# EEPROM.net
KiCad netlist of a schematic drawn in Altium Designer
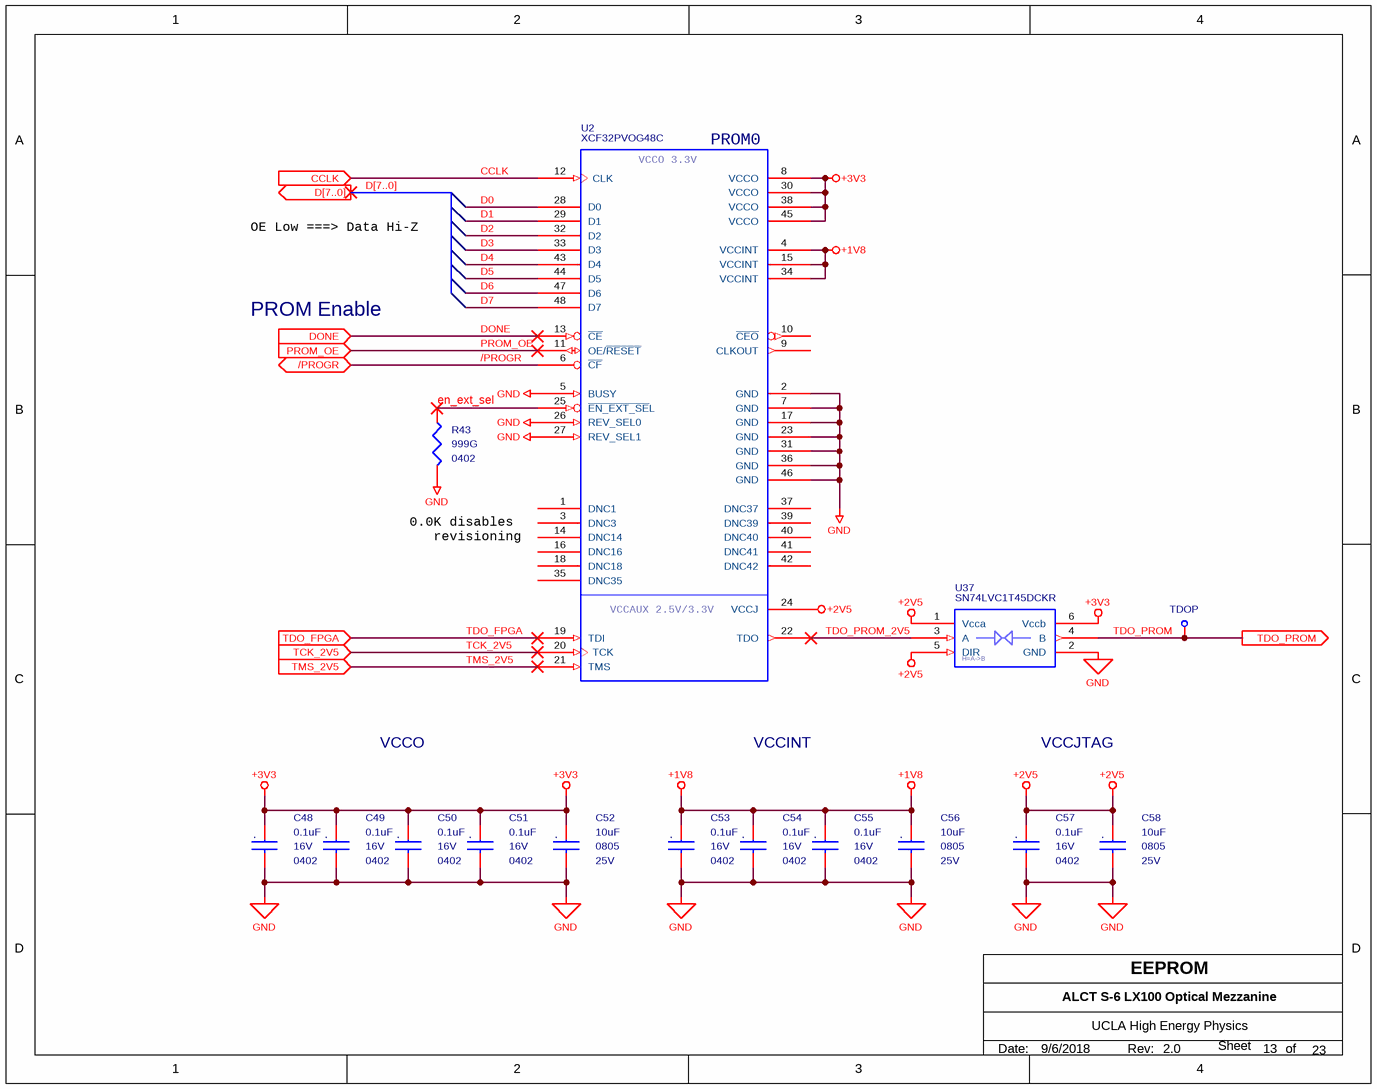
[diagram p0: EEPROM.SchDoc]

(export (version "E")
  (design (tool "Eeschema 10.0.6"))
  (components
    (comp (ref "C48")
      (value "0.1uF")
      (footprint "MC_S6/SM/C_0402_IPC")
      (description "CAP CER 0.1UF 16V X7R 0402")
      (fields
        (field (name "MANUFACTURER") "KEMET")
        (field (name "MANUFACTURER PART NUMBER") "C0402C104K4RACTU")
        (field (name "PACKAGE") "0402")
        (field (name "VOLTAGE - RATED") "16V")
      )
      (libsource (lib "ALCT_MEZ_SPARTAN6_Library") (part "C0402C104K4RACTU"))
    )
    (comp (ref "C49")
      (value "0.1uF")
      (footprint "MC_S6/SM/C_0402_IPC")
      (description "CAP CER 0.1UF 16V X7R 0402")
      (fields
        (field (name "MANUFACTURER") "KEMET")
        (field (name "MANUFACTURER PART NUMBER") "C0402C104K4RACTU")
        (field (name "PACKAGE") "0402")
        (field (name "VOLTAGE - RATED") "16V")
      )
      (libsource (lib "ALCT_MEZ_SPARTAN6_Library") (part "C0402C104K4RACTU"))
    )
    (comp (ref "C50")
      (value "0.1uF")
      (footprint "MC_S6/SM/C_0402_IPC")
      (description "CAP CER 0.1UF 16V X7R 0402")
      (fields
        (field (name "MANUFACTURER") "KEMET")
        (field (name "MANUFACTURER PART NUMBER") "C0402C104K4RACTU")
        (field (name "PACKAGE") "0402")
        (field (name "VOLTAGE - RATED") "16V")
      )
      (libsource (lib "ALCT_MEZ_SPARTAN6_Library") (part "C0402C104K4RACTU"))
    )
    (comp (ref "C51")
      (value "0.1uF")
      (footprint "MC_S6/SM/C_0402_IPC")
      (description "CAP CER 0.1UF 16V X7R 0402")
      (fields
        (field (name "MANUFACTURER") "KEMET")
        (field (name "MANUFACTURER PART NUMBER") "C0402C104K4RACTU")
        (field (name "PACKAGE") "0402")
        (field (name "VOLTAGE - RATED") "16V")
      )
      (libsource (lib "ALCT_MEZ_SPARTAN6_Library") (part "C0402C104K4RACTU"))
    )
    (comp (ref "C52")
      (value "10uF")
      (footprint "MC_S6/SM/C_0805_IPC")
      (description "CAP CER 10UF 25V X5R 0805")
      (fields
        (field (name "MANUFACTURER") "Murata Electronics North America")
        (field (name "MANUFACTURER PART NUMBER") "GRM21BR61E106KA73L")
        (field (name "VOLTAGE - RATED") "25V")
        (field (name "PACKAGE") "0805")
      )
      (libsource (lib "ALCT_MEZ_SPARTAN6_Library") (part "GRM21BR61E106KA73L"))
    )
    (comp (ref "C53")
      (value "0.1uF")
      (footprint "MC_S6/SM/C_0402_IPC")
      (description "CAP CER 0.1UF 16V X7R 0402")
      (fields
        (field (name "MANUFACTURER") "KEMET")
        (field (name "MANUFACTURER PART NUMBER") "C0402C104K4RACTU")
        (field (name "PACKAGE") "0402")
        (field (name "VOLTAGE - RATED") "16V")
      )
      (libsource (lib "ALCT_MEZ_SPARTAN6_Library") (part "C0402C104K4RACTU"))
    )
    (comp (ref "C54")
      (value "0.1uF")
      (footprint "MC_S6/SM/C_0402_IPC")
      (description "CAP CER 0.1UF 16V X7R 0402")
      (fields
        (field (name "MANUFACTURER") "KEMET")
        (field (name "MANUFACTURER PART NUMBER") "C0402C104K4RACTU")
        (field (name "PACKAGE") "0402")
        (field (name "VOLTAGE - RATED") "16V")
      )
      (libsource (lib "ALCT_MEZ_SPARTAN6_Library") (part "C0402C104K4RACTU"))
    )
    (comp (ref "C55")
      (value "0.1uF")
      (footprint "MC_S6/SM/C_0402_IPC")
      (description "CAP CER 0.1UF 16V X7R 0402")
      (fields
        (field (name "MANUFACTURER") "KEMET")
        (field (name "MANUFACTURER PART NUMBER") "C0402C104K4RACTU")
        (field (name "PACKAGE") "0402")
        (field (name "VOLTAGE - RATED") "16V")
      )
      (libsource (lib "ALCT_MEZ_SPARTAN6_Library") (part "C0402C104K4RACTU"))
    )
    (comp (ref "C56")
      (value "10uF")
      (footprint "MC_S6/SM/C_0805_IPC")
      (description "CAP CER 10UF 25V X5R 0805")
      (fields
        (field (name "MANUFACTURER") "Murata Electronics North America")
        (field (name "MANUFACTURER PART NUMBER") "GRM21BR61E106KA73L")
        (field (name "VOLTAGE - RATED") "25V")
        (field (name "PACKAGE") "0805")
      )
      (libsource (lib "ALCT_MEZ_SPARTAN6_Library") (part "GRM21BR61E106KA73L"))
    )
    (comp (ref "C57")
      (value "0.1uF")
      (footprint "MC_S6/SM/C_0402_IPC")
      (description "CAP CER 0.1UF 16V X7R 0402")
      (fields
        (field (name "MANUFACTURER") "KEMET")
        (field (name "MANUFACTURER PART NUMBER") "C0402C104K4RACTU")
        (field (name "PACKAGE") "0402")
        (field (name "VOLTAGE - RATED") "16V")
      )
      (libsource (lib "ALCT_MEZ_SPARTAN6_Library") (part "C0402C104K4RACTU"))
    )
    (comp (ref "C58")
      (value "10uF")
      (footprint "MC_S6/SM/C_0805_IPC")
      (description "CAP CER 10UF 25V X5R 0805")
      (fields
        (field (name "MANUFACTURER") "Murata Electronics North America")
        (field (name "MANUFACTURER PART NUMBER") "GRM21BR61E106KA73L")
        (field (name "VOLTAGE - RATED") "25V")
        (field (name "PACKAGE") "0805")
      )
      (libsource (lib "ALCT_MEZ_SPARTAN6_Library") (part "GRM21BR61E106KA73L"))
    )
    (comp (ref "R43")
      (value "999G")
      (footprint "MC_S6/SM/R_0402_IPC")
      (description "RES SMD 999G OHM 5% 1/16W 0402")
      (fields
        (field (name "MANUFACTURER PART NUMBER") "Do Not Place")
        (field (name "SUPPLIER DEVICE PACKAGE") "0402")
      )
      (libsource (lib "ALCT_MEZ_SPARTAN6_Library") (part "RES999G 0402"))
    )
    (comp (ref "TDOP")
      (value "Test Point Via")
      (footprint "MC_S6/TH/TPVIA")
      (libsource (lib "ALCT_MEZ_SPARTAN6_Library") (part "TPVIA"))
    )
    (comp (ref "U2")
      (value "XCF32PVOG48C")
      (footprint "MC_S6/SM/VOG48")
      (description "IC PROM SRL/PAR 1.8V 32M 48TSOP")
      (fields (field (name "MANUFACTURER") "Xilinx Inc."))
      (libsource (lib "ALCT_MEZ_SPARTAN6_Library") (part "XCF32PVOG48C"))
    )
    (comp (ref "U37")
      (value "SN74LVC1T45DCKR")
      (footprint "MC_S6/SM/SOT_SC70_DCK6")
      (description "IC BUS TRANSCVR TRI-ST SC70-6")
      (fields (field (name "MANUFACTURER") "Texas Instruments"))
      (libsource (lib "ALCT_MEZ_SPARTAN6_Library") (part "SN74LVC1T45-EP-ALCT_1"))
    )
  )
  (nets
    (net (code "1") (name "+1V8") (class "Default")
      (node (ref "C53") (pin "1") (pinfunction "1_1") (pintype "passive"))
      (node (ref "C54") (pin "1") (pinfunction "1_1") (pintype "passive"))
      (node (ref "C55") (pin "1") (pinfunction "1_1") (pintype "passive"))
      (node (ref "C56") (pin "1") (pinfunction "1_1") (pintype "passive"))
      (node (ref "U2") (pin "15") (pinfunction "VCCINT_15") (pintype "power_in"))
      (node (ref "U2") (pin "34") (pinfunction "VCCINT_34") (pintype "power_in"))
      (node (ref "U2") (pin "4") (pinfunction "VCCINT_4") (pintype "power_in"))
    )
    (net (code "2") (name "+2V5") (class "Default")
      (node (ref "C57") (pin "1") (pinfunction "1_1") (pintype "passive"))
      (node (ref "C58") (pin "1") (pinfunction "1_1") (pintype "passive"))
      (node (ref "U2") (pin "24") (pinfunction "VCCJ_24") (pintype "power_in"))
      (node (ref "U37") (pin "1") (pinfunction "Vcca_1") (pintype "power_in"))
      (node (ref "U37") (pin "5") (pinfunction "DIR_5") (pintype "input"))
    )
    (net (code "3") (name "+3V3") (class "Default")
      (node (ref "C48") (pin "1") (pinfunction "1_1") (pintype "passive"))
      (node (ref "C49") (pin "1") (pinfunction "1_1") (pintype "passive"))
      (node (ref "C50") (pin "1") (pinfunction "1_1") (pintype "passive"))
      (node (ref "C51") (pin "1") (pinfunction "1_1") (pintype "passive"))
      (node (ref "C52") (pin "1") (pinfunction "1_1") (pintype "passive"))
      (node (ref "U2") (pin "30") (pinfunction "VCCO_30") (pintype "power_in"))
      (node (ref "U2") (pin "38") (pinfunction "VCCO_38") (pintype "power_in"))
      (node (ref "U2") (pin "45") (pinfunction "VCCO_45") (pintype "power_in"))
      (node (ref "U2") (pin "8") (pinfunction "VCCO_8") (pintype "power_in"))
      (node (ref "U37") (pin "6") (pinfunction "Vccb_6") (pintype "power_in"))
    )
    (net (code "4") (name "/CCLK") (class "Default")
      (node (ref "U2") (pin "12") (pinfunction "CLK_12") (pintype "input"))
    )
    (net (code "5") (name "/D0") (class "Default")
      (node (ref "U2") (pin "28") (pinfunction "D0_28") (pintype "tri_state"))
    )
    (net (code "6") (name "/D1") (class "Default")
      (node (ref "U2") (pin "29") (pinfunction "D1_29") (pintype "tri_state"))
    )
    (net (code "7") (name "/D2") (class "Default")
      (node (ref "U2") (pin "32") (pinfunction "D2_32") (pintype "tri_state"))
    )
    (net (code "8") (name "/D3") (class "Default")
      (node (ref "U2") (pin "33") (pinfunction "D3_33") (pintype "tri_state"))
    )
    (net (code "9") (name "/D4") (class "Default")
      (node (ref "U2") (pin "43") (pinfunction "D4_43") (pintype "tri_state"))
    )
    (net (code "10") (name "/D5") (class "Default")
      (node (ref "U2") (pin "44") (pinfunction "D5_44") (pintype "tri_state"))
    )
    (net (code "11") (name "/D6") (class "Default")
      (node (ref "U2") (pin "47") (pinfunction "D6_47") (pintype "tri_state"))
    )
    (net (code "12") (name "/D7") (class "Default")
      (node (ref "U2") (pin "48") (pinfunction "D7_48") (pintype "tri_state"))
    )
    (net (code "13") (name "/DONE") (class "Default")
      (node (ref "U2") (pin "13") (pinfunction "~{CE}_13") (pintype "input+no_connect"))
    )
    (net (code "15") (name "/PROM_OE") (class "Default")
      (node (ref "U2") (pin "11") (pinfunction "OE/~{RESET}_11") (pintype "bidirectional+no_connect"))
    )
    (net (code "16") (name "/TCK_2V5") (class "Default")
      (node (ref "U2") (pin "20") (pinfunction "TCK_20") (pintype "input+no_connect"))
    )
    (net (code "17") (name "/TDO_FPGA") (class "Default")
      (node (ref "U2") (pin "19") (pinfunction "TDI_19") (pintype "input+no_connect"))
    )
    (net (code "18") (name "/TDO_PROM") (class "Default")
      (node (ref "TDOP") (pin "1") (pinfunction "In_1") (pintype "passive"))
      (node (ref "U37") (pin "4") (pinfunction "B_4") (pintype "output"))
    )
    (net (code "19") (name "/TDO_PROM_2V5") (class "Default")
      (node (ref "U2") (pin "22") (pinfunction "TDO_22") (pintype "output"))
      (node (ref "U37") (pin "3") (pinfunction "A_3") (pintype "input"))
    )
    (net (code "20") (name "/TMS_2V5") (class "Default")
      (node (ref "U2") (pin "21") (pinfunction "TMS_21") (pintype "input+no_connect"))
    )
    (net (code "21") (name "/en_ext_sel") (class "Default")
      (node (ref "R43") (pin "1") (pinfunction "1_1") (pintype "passive"))
      (node (ref "U2") (pin "25") (pinfunction "~{EN_EXT_SE}L_25") (pintype "input"))
    )
    (net (code "22") (name "/{slash}PROGR") (class "Default")
      (node (ref "U2") (pin "6") (pinfunction "~{CF}_6") (pintype "open_collector"))
    )
    (net (code "23") (name "GND") (class "Default")
      (node (ref "C48") (pin "2") (pinfunction "2_2") (pintype "passive"))
      (node (ref "C49") (pin "2") (pinfunction "2_2") (pintype "passive"))
      (node (ref "C50") (pin "2") (pinfunction "2_2") (pintype "passive"))
      (node (ref "C51") (pin "2") (pinfunction "2_2") (pintype "passive"))
      (node (ref "C52") (pin "2") (pinfunction "2_2") (pintype "passive"))
      (node (ref "C53") (pin "2") (pinfunction "2_2") (pintype "passive"))
      (node (ref "C54") (pin "2") (pinfunction "2_2") (pintype "passive"))
      (node (ref "C55") (pin "2") (pinfunction "2_2") (pintype "passive"))
      (node (ref "C56") (pin "2") (pinfunction "2_2") (pintype "passive"))
      (node (ref "C57") (pin "2") (pinfunction "2_2") (pintype "passive"))
      (node (ref "C58") (pin "2") (pinfunction "2_2") (pintype "passive"))
      (node (ref "R43") (pin "2") (pinfunction "2_2") (pintype "passive"))
      (node (ref "U2") (pin "17") (pinfunction "GND_17") (pintype "power_in"))
      (node (ref "U2") (pin "2") (pinfunction "GND_2") (pintype "power_in"))
      (node (ref "U2") (pin "23") (pinfunction "GND_23") (pintype "power_in"))
      (node (ref "U2") (pin "26") (pinfunction "REV_SEL0_26") (pintype "input"))
      (node (ref "U2") (pin "27") (pinfunction "REV_SEL1_27") (pintype "input"))
      (node (ref "U2") (pin "31") (pinfunction "GND_31") (pintype "power_in"))
      (node (ref "U2") (pin "36") (pinfunction "GND_36") (pintype "power_in"))
      (node (ref "U2") (pin "46") (pinfunction "GND_46") (pintype "power_in"))
      (node (ref "U2") (pin "5") (pinfunction "BUSY_5") (pintype "input"))
      (node (ref "U2") (pin "7") (pinfunction "GND_7") (pintype "power_in"))
      (node (ref "U37") (pin "2") (pinfunction "GND_2") (pintype "power_in"))
    )
    (net (code "24") (name "unconnected-(U2-CLKOUT-Pad9)") (class "Default")
      (node (ref "U2") (pin "9") (pinfunction "CLKOUT_9") (pintype "output"))
    )
    (net (code "25") (name "unconnected-(U2-DNC1-Pad1)") (class "Default")
      (node (ref "U2") (pin "1") (pinfunction "DNC1_1") (pintype "passive"))
    )
    (net (code "26") (name "unconnected-(U2-DNC3-Pad3)") (class "Default")
      (node (ref "U2") (pin "3") (pinfunction "DNC3_3") (pintype "passive"))
    )
    (net (code "27") (name "unconnected-(U2-DNC14-Pad14)") (class "Default")
      (node (ref "U2") (pin "14") (pinfunction "DNC14_14") (pintype "passive"))
    )
    (net (code "28") (name "unconnected-(U2-DNC16-Pad16)") (class "Default")
      (node (ref "U2") (pin "16") (pinfunction "DNC16_16") (pintype "passive"))
    )
    (net (code "29") (name "unconnected-(U2-DNC18-Pad18)") (class "Default")
      (node (ref "U2") (pin "18") (pinfunction "DNC18_18") (pintype "passive"))
    )
    (net (code "30") (name "unconnected-(U2-DNC35-Pad35)") (class "Default")
      (node (ref "U2") (pin "35") (pinfunction "DNC35_35") (pintype "passive"))
    )
    (net (code "31") (name "unconnected-(U2-DNC37-Pad37)") (class "Default")
      (node (ref "U2") (pin "37") (pinfunction "DNC37_37") (pintype "passive"))
    )
    (net (code "32") (name "unconnected-(U2-DNC39-Pad39)") (class "Default")
      (node (ref "U2") (pin "39") (pinfunction "DNC39_39") (pintype "passive"))
    )
    (net (code "33") (name "unconnected-(U2-DNC40-Pad40)") (class "Default")
      (node (ref "U2") (pin "40") (pinfunction "DNC40_40") (pintype "passive"))
    )
    (net (code "34") (name "unconnected-(U2-DNC41-Pad41)") (class "Default")
      (node (ref "U2") (pin "41") (pinfunction "DNC41_41") (pintype "passive"))
    )
    (net (code "35") (name "unconnected-(U2-DNC42-Pad42)") (class "Default")
      (node (ref "U2") (pin "42") (pinfunction "DNC42_42") (pintype "passive"))
    )
    (net (code "36") (name "unconnected-(U2-~{CEO}-Pad10)") (class "Default")
      (node (ref "U2") (pin "10") (pinfunction "~{CEO}_10") (pintype "output"))
    )
  )
)
